# ww101board.net
KiCad netlist of a schematic drawn in EAGLE
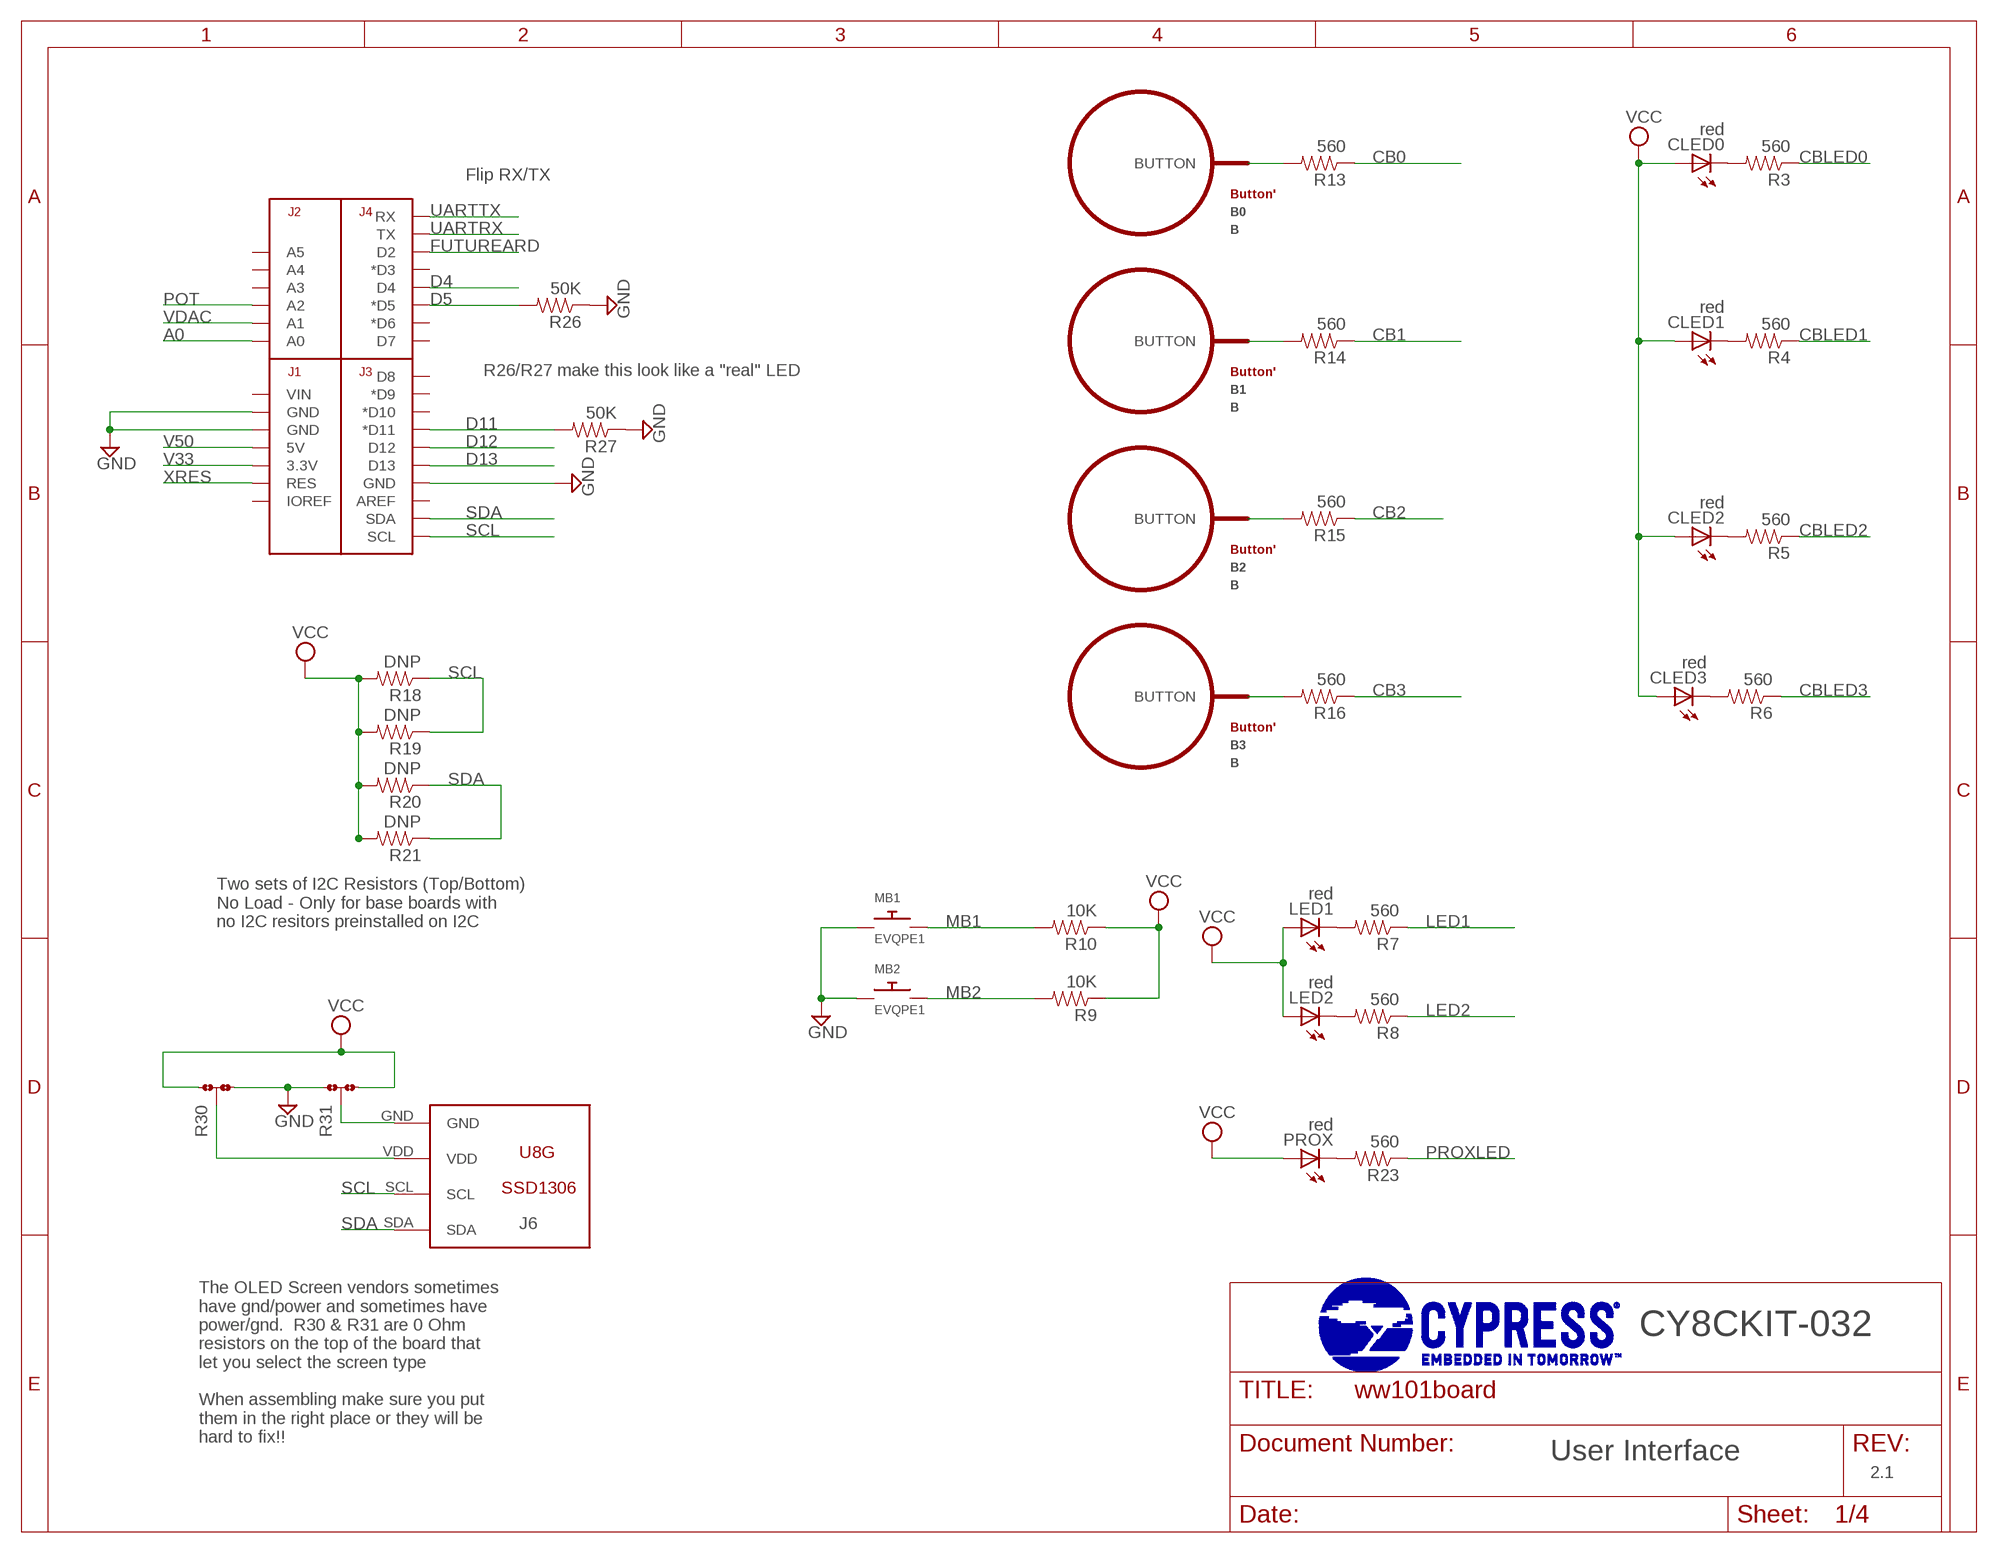
[diagram p0: schematic, sheet 1]
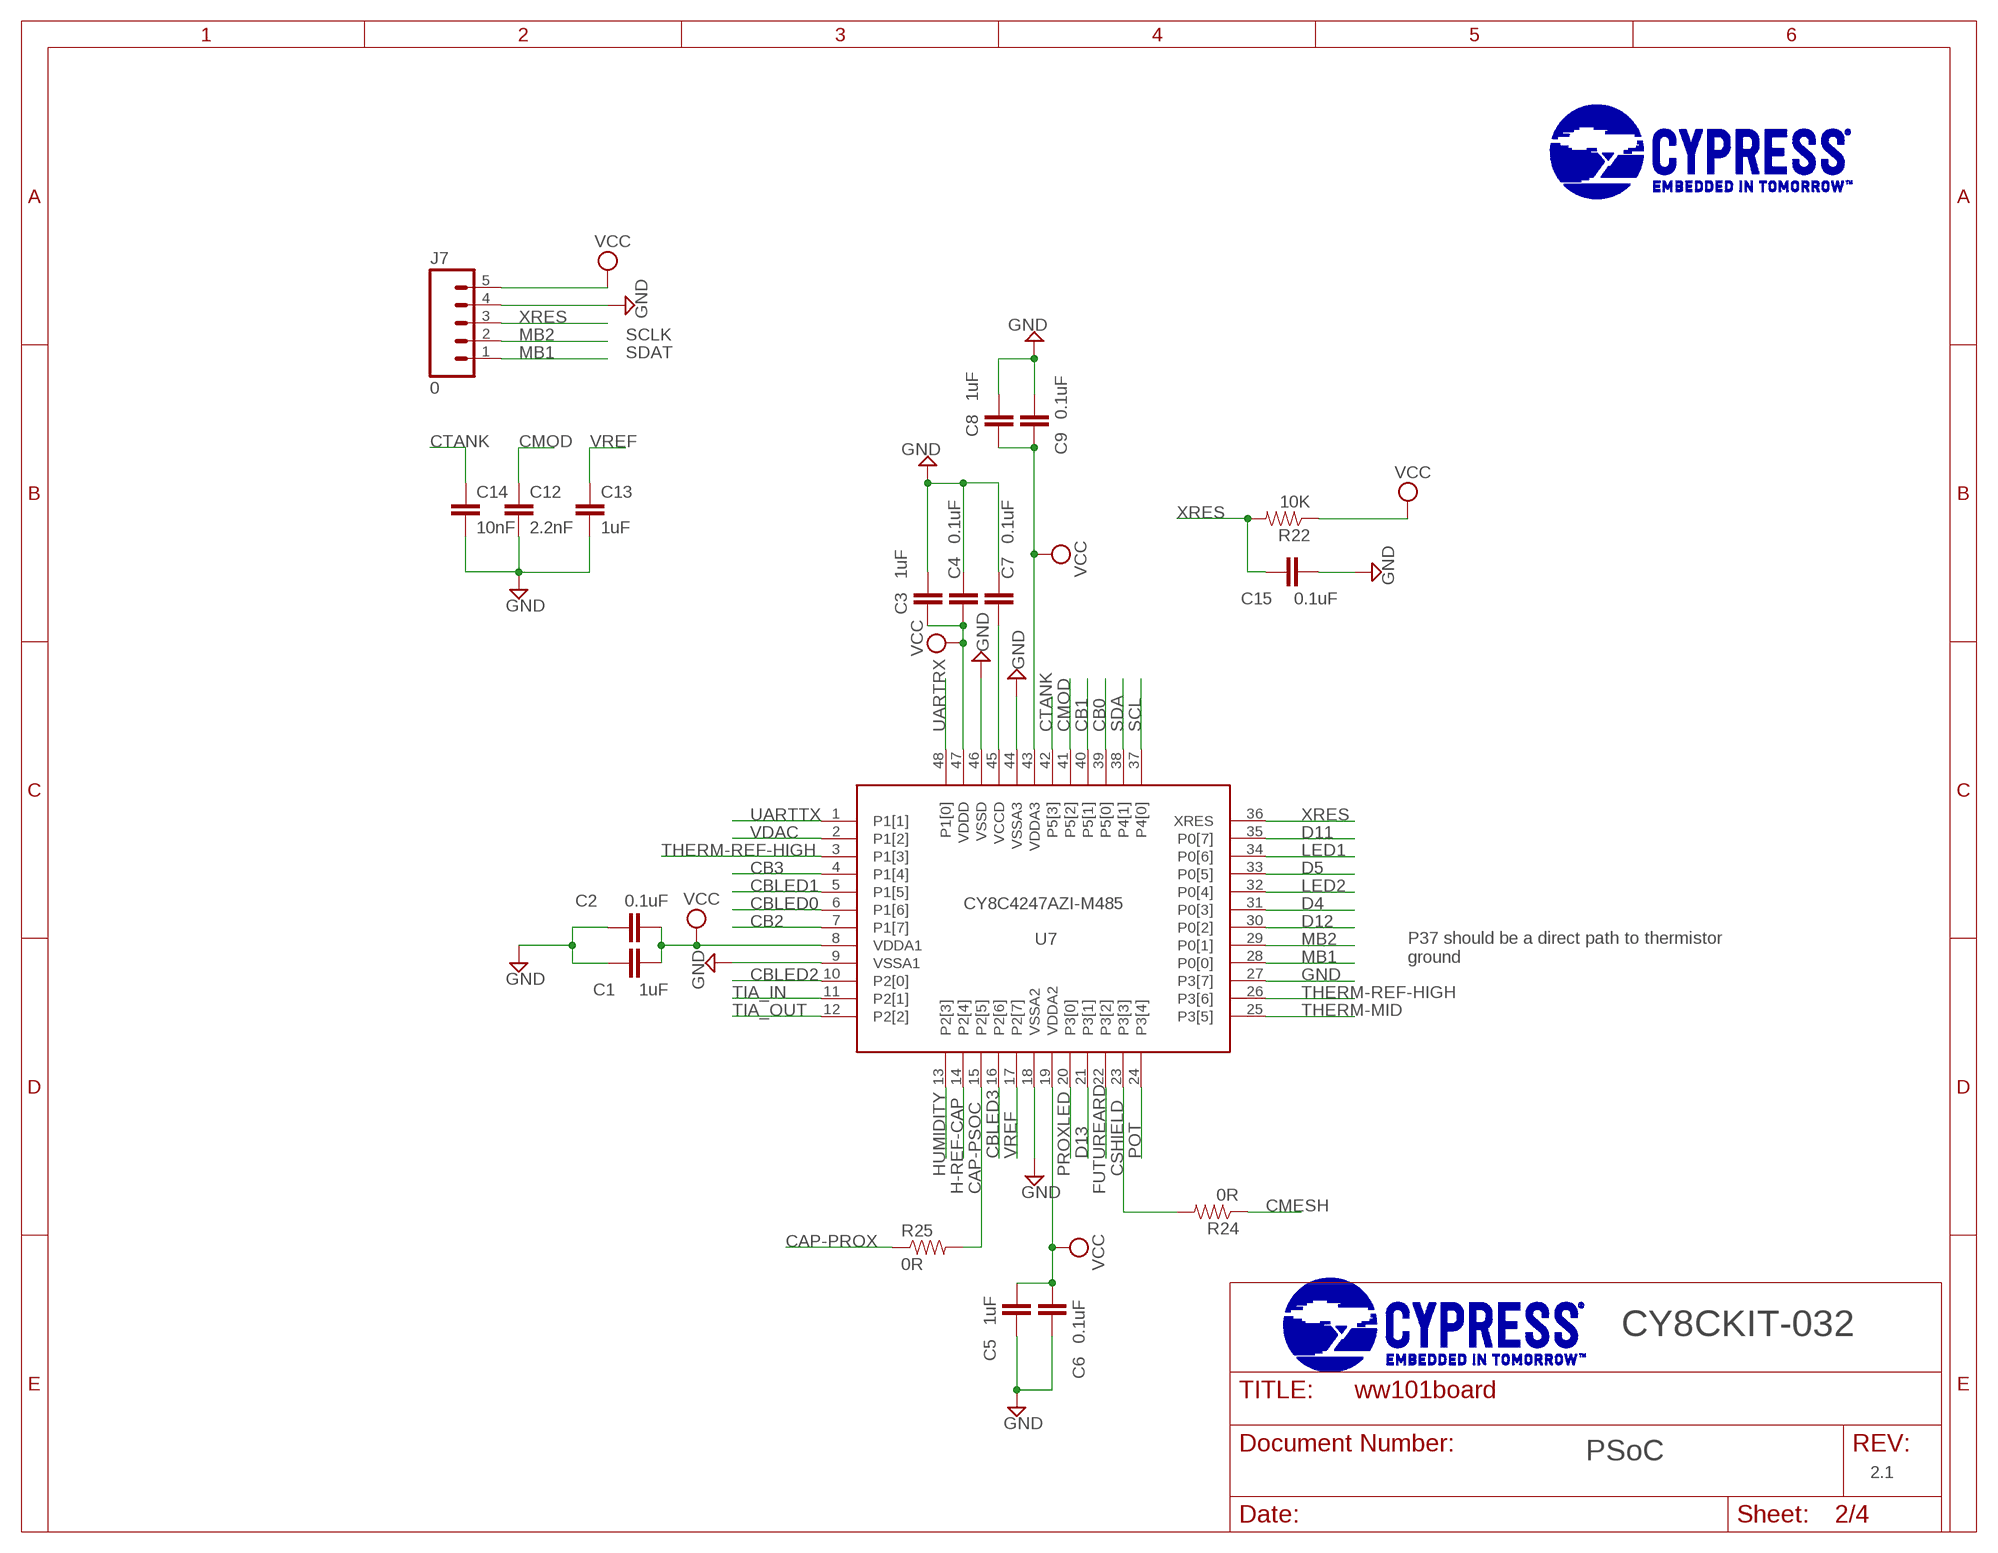
[diagram p1: schematic, sheet 2]
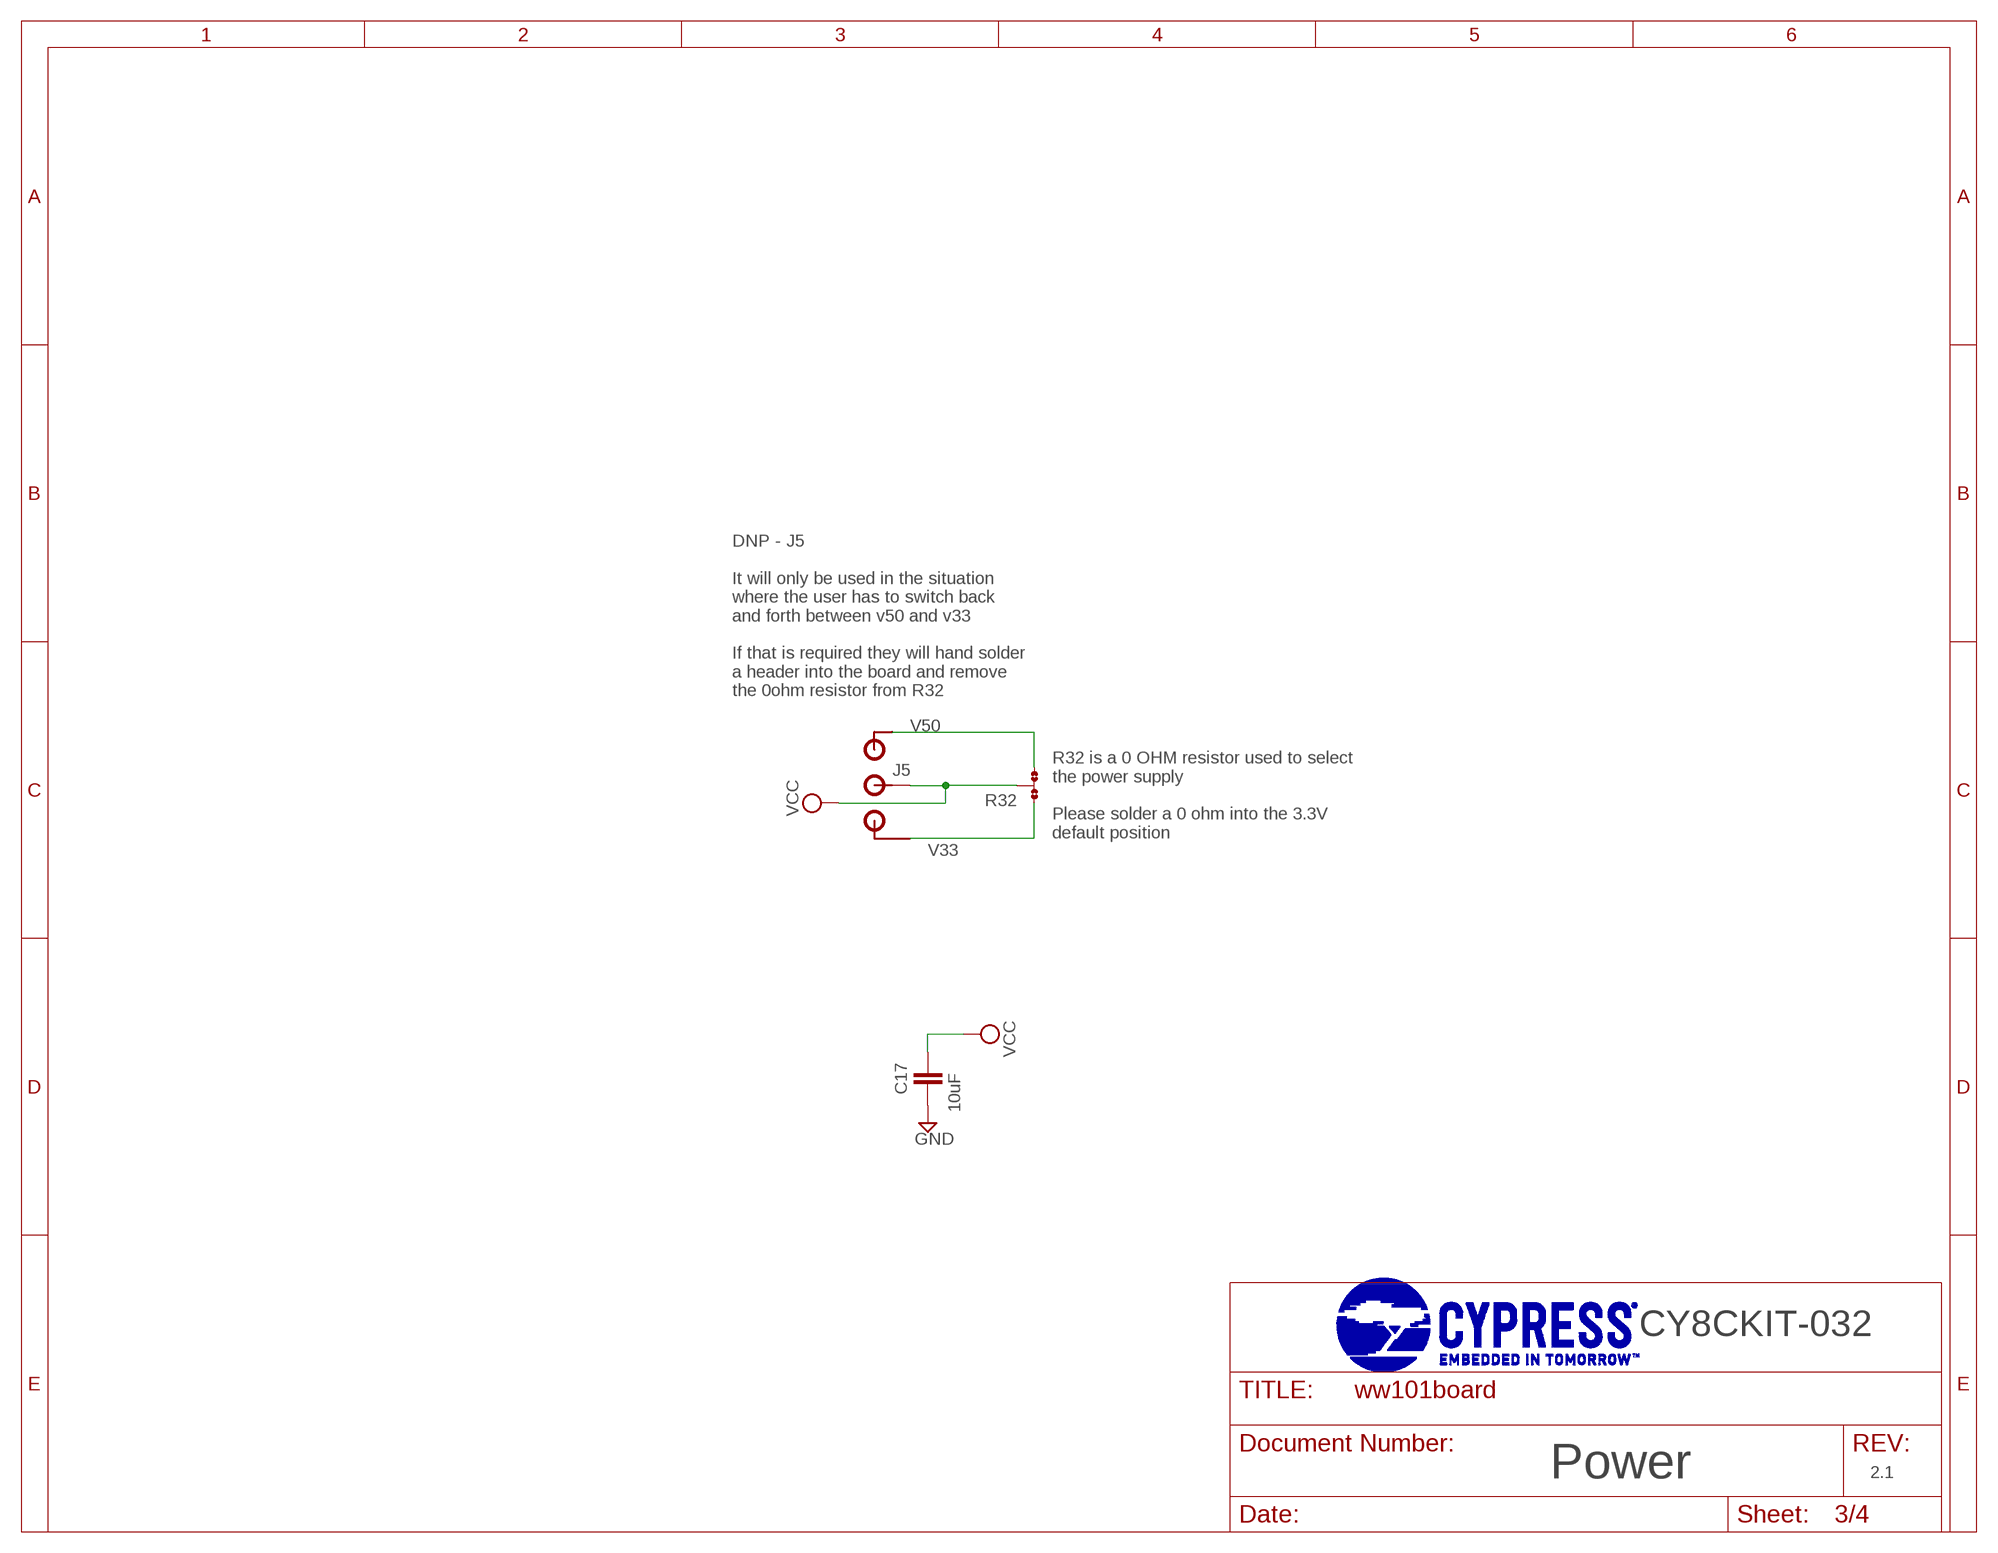
[diagram p2: schematic, sheet 3]
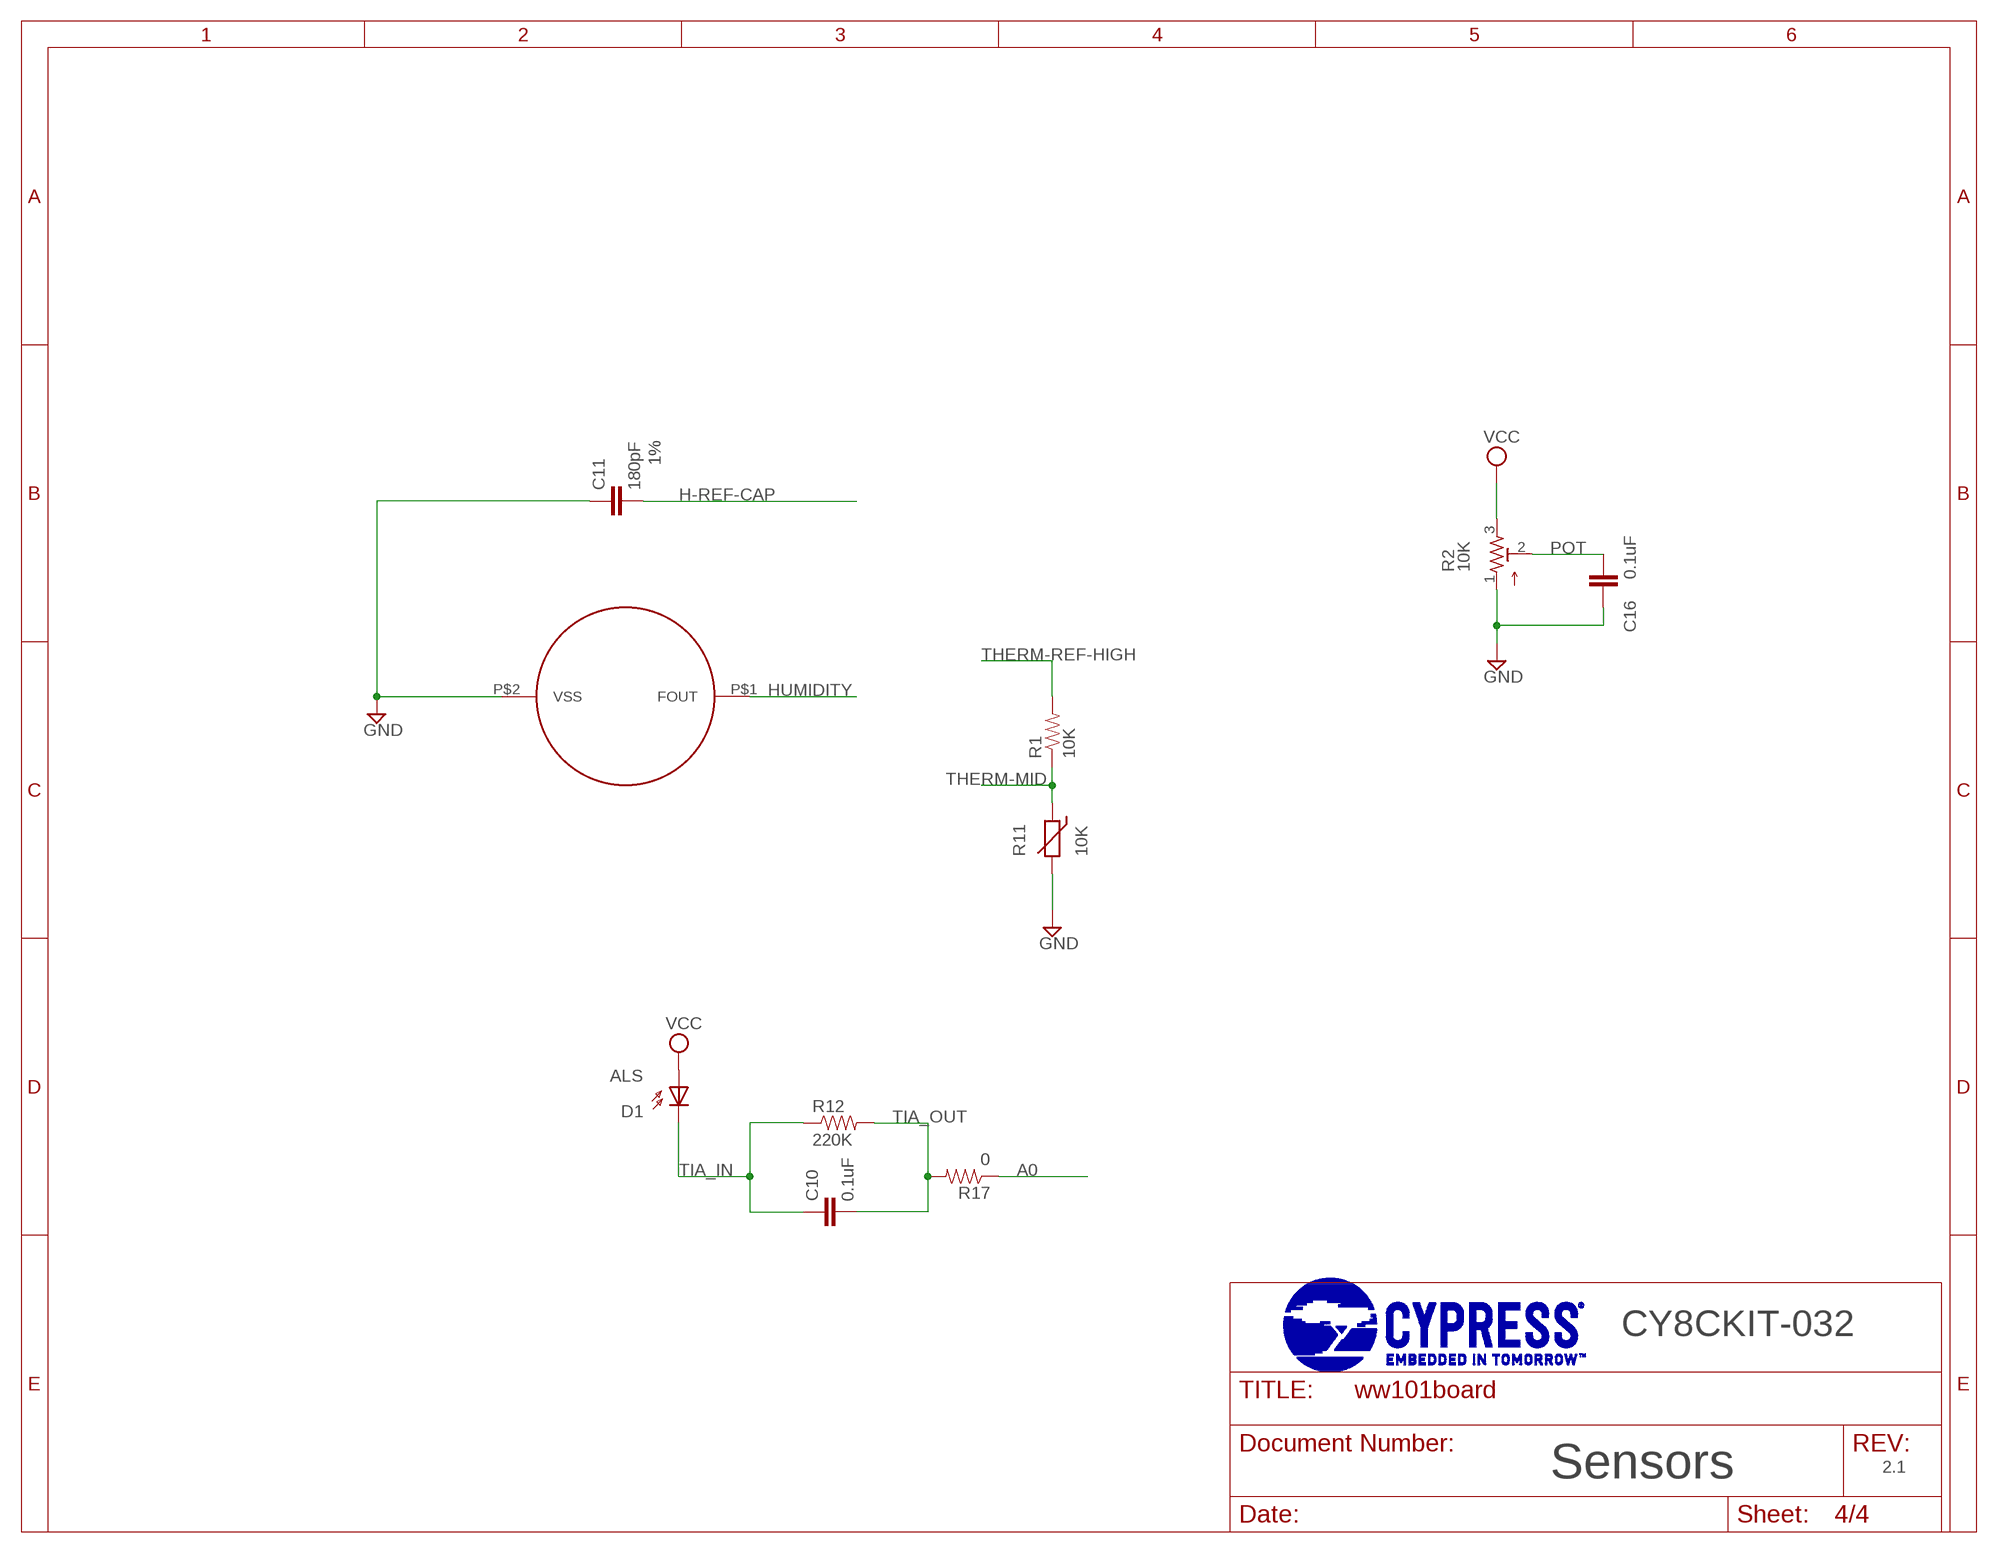
[diagram p3: schematic, sheet 4]

(export (version "E")
  (design (tool "Eeschema 10.0.6"))
  (components
    (comp (ref "C10")
      (value "0.1uF")
      (footprint "eagle-import:0603-CAP")
      (libsource (lib "eagle-import") (part "CAP0603-CAP"))
    )
    (comp (ref "C11")
      (value "180pF")
      (footprint "eagle-import:0603-CAP")
      (libsource (lib "eagle-import") (part "CAP0603-CAP"))
    )
    (comp (ref "C16")
      (value "0.1uF")
      (footprint "eagle-import:0603-CAP")
      (libsource (lib "eagle-import") (part "CAP0603-CAP"))
    )
    (comp (ref "D1")
      (value "ALS")
      (footprint "eagle-import:ALS")
      (libsource (lib "eagle-import") (part "ALS"))
    )
    (comp (ref "HUMIDITY")
      (value "HPP801A031")
      (footprint "eagle-import:HUMIDITY")
      (libsource (lib "eagle-import") (part "HPP801A031"))
    )
    (comp (ref "R1")
      (value "10K")
      (footprint "eagle-import:0603-RES")
      (libsource (lib "eagle-import") (part "RESISTOR0603"))
    )
    (comp (ref "R2")
      (value "10K")
      (footprint "eagle-import:3386P")
      (libsource (lib "eagle-import") (part "TRIM_US-3386P"))
    )
    (comp (ref "R11")
      (value "THERMISTOR-5")
      (footprint "eagle-import:R-5")
      (libsource (lib "eagle-import") (part "THERMISTOR-5"))
    )
    (comp (ref "R12")
      (value "220K")
      (footprint "eagle-import:0603-RES")
      (libsource (lib "eagle-import") (part "RESISTOR0603"))
    )
    (comp (ref "R17")
      (value "0")
      (footprint "eagle-import:0603-RES")
      (libsource (lib "eagle-import") (part "RESISTOR0603"))
    )
    (comp (ref "B0")
      (value "B")
      (footprint "eagle-import:BUTTON_PASSIVE_10MM")
      (libsource (lib "eagle-import") (part "BUTTON_PASSIVE10MM"))
    )
    (comp (ref "B1")
      (value "B")
      (footprint "eagle-import:BUTTON_PASSIVE_10MM")
      (libsource (lib "eagle-import") (part "BUTTON_PASSIVE10MM"))
    )
    (comp (ref "B2")
      (value "B")
      (footprint "eagle-import:BUTTON_PASSIVE_10MM")
      (libsource (lib "eagle-import") (part "BUTTON_PASSIVE10MM"))
    )
    (comp (ref "B3")
      (value "B")
      (footprint "eagle-import:BUTTON_PASSIVE_10MM")
      (libsource (lib "eagle-import") (part "BUTTON_PASSIVE10MM"))
    )
    (comp (ref "CLED0")
      (value "red")
      (footprint "eagle-import:CHIP-LED0603")
      (libsource (lib "eagle-import") (part "LEDCHIP-LED0603"))
    )
    (comp (ref "CLED1")
      (value "red")
      (footprint "eagle-import:CHIP-LED0603")
      (libsource (lib "eagle-import") (part "LEDCHIP-LED0603"))
    )
    (comp (ref "CLED2")
      (value "red")
      (footprint "eagle-import:CHIP-LED0603")
      (libsource (lib "eagle-import") (part "LEDCHIP-LED0603"))
    )
    (comp (ref "CLED3")
      (value "red")
      (footprint "eagle-import:CHIP-LED0603")
      (libsource (lib "eagle-import") (part "LEDCHIP-LED0603"))
    )
    (comp (ref "J6")
      (value "U8G-096-OLED")
      (footprint "eagle-import:096-SSD1306")
      (libsource (lib "eagle-import") (part "U8G-096-OLED"))
    )
    (comp (ref "LED1")
      (value "red")
      (footprint "eagle-import:CHIP-LED0603")
      (libsource (lib "eagle-import") (part "LEDCHIP-LED0603"))
    )
    (comp (ref "LED2")
      (value "red")
      (footprint "eagle-import:CHIP-LED0603")
      (libsource (lib "eagle-import") (part "LEDCHIP-LED0603"))
    )
    (comp (ref "MB1")
      (value "EVQPE1")
      (footprint "eagle-import:SWITCH")
      (libsource (lib "eagle-import") (part "EVQPE1"))
    )
    (comp (ref "MB2")
      (value "EVQPE1")
      (footprint "eagle-import:SWITCH")
      (libsource (lib "eagle-import") (part "EVQPE1"))
    )
    (comp (ref "PROX")
      (value "red")
      (footprint "eagle-import:CHIP-LED0603")
      (libsource (lib "eagle-import") (part "LEDCHIP-LED0603"))
    )
    (comp (ref "R3")
      (value "560")
      (footprint "eagle-import:0603-RES")
      (libsource (lib "eagle-import") (part "RESISTOR0603"))
    )
    (comp (ref "R4")
      (value "560")
      (footprint "eagle-import:0603-RES")
      (libsource (lib "eagle-import") (part "RESISTOR0603"))
    )
    (comp (ref "R5")
      (value "560")
      (footprint "eagle-import:0603-RES")
      (libsource (lib "eagle-import") (part "RESISTOR0603"))
    )
    (comp (ref "R6")
      (value "560")
      (footprint "eagle-import:0603-RES")
      (libsource (lib "eagle-import") (part "RESISTOR0603"))
    )
    (comp (ref "R7")
      (value "560")
      (footprint "eagle-import:0603-RES")
      (libsource (lib "eagle-import") (part "RESISTOR0603"))
    )
    (comp (ref "R8")
      (value "560")
      (footprint "eagle-import:0603-RES")
      (libsource (lib "eagle-import") (part "RESISTOR0603"))
    )
    (comp (ref "R9")
      (value "10K")
      (footprint "eagle-import:0603-RES")
      (libsource (lib "eagle-import") (part "RESISTOR0603"))
    )
    (comp (ref "R10")
      (value "10K")
      (footprint "eagle-import:0603-RES")
      (libsource (lib "eagle-import") (part "RESISTOR0603"))
    )
    (comp (ref "R13")
      (value "560")
      (footprint "eagle-import:0603-RES")
      (libsource (lib "eagle-import") (part "RESISTOR0603"))
    )
    (comp (ref "R14")
      (value "560")
      (footprint "eagle-import:0603-RES")
      (libsource (lib "eagle-import") (part "RESISTOR0603"))
    )
    (comp (ref "R15")
      (value "560")
      (footprint "eagle-import:0603-RES")
      (libsource (lib "eagle-import") (part "RESISTOR0603"))
    )
    (comp (ref "R16")
      (value "560")
      (footprint "eagle-import:0603-RES")
      (libsource (lib "eagle-import") (part "RESISTOR0603"))
    )
    (comp (ref "R18")
      (value "DNP")
      (footprint "eagle-import:0603-RES")
      (libsource (lib "eagle-import") (part "RESISTOR0603"))
    )
    (comp (ref "R19")
      (value "DNP")
      (footprint "eagle-import:0603-RES")
      (libsource (lib "eagle-import") (part "RESISTOR0603"))
    )
    (comp (ref "R20")
      (value "DNP")
      (footprint "eagle-import:0603-RES")
      (libsource (lib "eagle-import") (part "RESISTOR0603"))
    )
    (comp (ref "R21")
      (value "DNP")
      (footprint "eagle-import:0603-RES")
      (libsource (lib "eagle-import") (part "RESISTOR0603"))
    )
    (comp (ref "R23")
      (value "560")
      (footprint "eagle-import:0603-RES")
      (libsource (lib "eagle-import") (part "RESISTOR0603"))
    )
    (comp (ref "R26")
      (value "50K")
      (footprint "eagle-import:0603-RES")
      (libsource (lib "eagle-import") (part "RESISTOR0603"))
    )
    (comp (ref "R27")
      (value "50K")
      (footprint "eagle-import:0603-RES")
      (libsource (lib "eagle-import") (part "RESISTOR0603"))
    )
    (comp (ref "R30")
      (value "JMP-3-1_2")
      (footprint "eagle-import:JMP-3-1_2")
      (libsource (lib "eagle-import") (part "JMP-3-1_2"))
    )
    (comp (ref "R31")
      (value "JMP-3-2_3")
      (footprint "eagle-import:JMP-3-2_3")
      (libsource (lib "eagle-import") (part "JMP-3-2_3"))
    )
    (comp (ref "U$1")
      (value "ARDUINO_R3_SHIELDNOLABELS")
      (footprint "eagle-import:UNO_R3_SHIELD_NOLABELS")
      (libsource (lib "eagle-import") (part "ARDUINO_R3_SHIELDNOLABELS"))
    )
    (comp (ref "C1")
      (value "1uF")
      (footprint "eagle-import:0603-CAP")
      (libsource (lib "eagle-import") (part "CAP0603-CAP"))
    )
    (comp (ref "C2")
      (value "0.1uF")
      (footprint "eagle-import:0603-CAP")
      (libsource (lib "eagle-import") (part "CAP0603-CAP"))
    )
    (comp (ref "C3")
      (value "1uF")
      (footprint "eagle-import:0603-CAP")
      (libsource (lib "eagle-import") (part "CAP0603-CAP"))
    )
    (comp (ref "C4")
      (value "0.1uF")
      (footprint "eagle-import:0603-CAP")
      (libsource (lib "eagle-import") (part "CAP0603-CAP"))
    )
    (comp (ref "C5")
      (value "1uF")
      (footprint "eagle-import:0603-CAP")
      (libsource (lib "eagle-import") (part "CAP0603-CAP"))
    )
    (comp (ref "C6")
      (value "0.1uF")
      (footprint "eagle-import:0603-CAP")
      (libsource (lib "eagle-import") (part "CAP0603-CAP"))
    )
    (comp (ref "C7")
      (value "0.1uF")
      (footprint "eagle-import:0603-CAP")
      (libsource (lib "eagle-import") (part "CAP0603-CAP"))
    )
    (comp (ref "C8")
      (value "1uF")
      (footprint "eagle-import:0603-CAP")
      (libsource (lib "eagle-import") (part "CAP0603-CAP"))
    )
    (comp (ref "C9")
      (value "0.1uF")
      (footprint "eagle-import:0603-CAP")
      (libsource (lib "eagle-import") (part "CAP0603-CAP"))
    )
    (comp (ref "C12")
      (value "2.2nF")
      (footprint "eagle-import:0603-CAP")
      (libsource (lib "eagle-import") (part "CAP0603-CAP"))
    )
    (comp (ref "C13")
      (value "1uF")
      (footprint "eagle-import:0603-CAP")
      (libsource (lib "eagle-import") (part "CAP0603-CAP"))
    )
    (comp (ref "C14")
      (value "10nF")
      (footprint "eagle-import:0603-CAP")
      (libsource (lib "eagle-import") (part "CAP0603-CAP"))
    )
    (comp (ref "C15")
      (value "0.1uF")
      (footprint "eagle-import:0603-CAP")
      (libsource (lib "eagle-import") (part "CAP0603-CAP"))
    )
    (comp (ref "J7")
      (value "0")
      (footprint "eagle-import:1X05_LOCK")
      (libsource (lib "eagle-import") (part "M05LOCK"))
    )
    (comp (ref "R22")
      (value "10K")
      (footprint "eagle-import:0603-RES")
      (libsource (lib "eagle-import") (part "RESISTOR0603"))
    )
    (comp (ref "R24")
      (value "0R")
      (footprint "eagle-import:0603-RES")
      (libsource (lib "eagle-import") (part "RESISTOR0603"))
    )
    (comp (ref "R25")
      (value "0R")
      (footprint "eagle-import:0603-RES")
      (libsource (lib "eagle-import") (part "RESISTOR0603"))
    )
    (comp (ref "U$7")
      (value "CYLOGO-SILK")
      (footprint "eagle-import:CYLOGO-SILK")
      (libsource (lib "eagle-import") (part "CYLOGO-SILK"))
    )
    (comp (ref "U7")
      (value "CY8C4A45-48")
      (footprint "eagle-import:TQFP-7X7-48")
      (libsource (lib "eagle-import") (part "CY8C4A45-48"))
    )
    (comp (ref "C17")
      (value "10uF")
      (footprint "eagle-import:0603-CAP")
      (libsource (lib "eagle-import") (part "CAP0603-CAP"))
    )
    (comp (ref "J5")
      (value "JMP-3-PTH-PTH")
      (footprint "eagle-import:JMP-3-NO-PTH-2.54")
      (libsource (lib "eagle-import") (part "JMP-3-PTH-PTH"))
    )
    (comp (ref "R32")
      (value "JMP-3-NO")
      (footprint "eagle-import:JMP-3-NO")
      (libsource (lib "eagle-import") (part "JMP-3-NO"))
    )
  )
  (nets
    (net (code "1") (name "A0") (class "Default")
      (node (ref "R17") (pin "1") (pinfunction "1_1") (pintype "passive"))
      (node (ref "U$1") (pin "A0") (pinfunction "A0_A0") (pintype "bidirectional"))
    )
    (net (code "2") (name "CAP-PROX") (class "Default")
      (node (ref "R25") (pin "1") (pinfunction "1_1") (pintype "passive"))
    )
    (net (code "3") (name "CAP-PSOC") (class "Default")
      (node (ref "R25") (pin "2") (pinfunction "2_2") (pintype "passive"))
      (node (ref "U7") (pin "15") (pinfunction "P2[5]_15") (pintype "bidirectional"))
    )
    (net (code "4") (name "CB0") (class "Default")
      (node (ref "R13") (pin "1") (pinfunction "1_1") (pintype "passive"))
      (node (ref "U7") (pin "39") (pinfunction "P5[0]_39") (pintype "bidirectional"))
    )
    (net (code "5") (name "CB1") (class "Default")
      (node (ref "R14") (pin "1") (pinfunction "1_1") (pintype "passive"))
      (node (ref "U7") (pin "40") (pinfunction "P5[1]_40") (pintype "bidirectional"))
    )
    (net (code "6") (name "CB2") (class "Default")
      (node (ref "R15") (pin "1") (pinfunction "1_1") (pintype "passive"))
      (node (ref "U7") (pin "7") (pinfunction "P1[7]_7") (pintype "bidirectional"))
    )
    (net (code "7") (name "CB3") (class "Default")
      (node (ref "R16") (pin "1") (pinfunction "1_1") (pintype "passive"))
      (node (ref "U7") (pin "4") (pinfunction "P1[4]_4") (pintype "bidirectional"))
    )
    (net (code "8") (name "CBLED0") (class "Default")
      (node (ref "R3") (pin "1") (pinfunction "1_1") (pintype "passive"))
      (node (ref "U7") (pin "6") (pinfunction "P1[6]_6") (pintype "bidirectional"))
    )
    (net (code "9") (name "CBLED1") (class "Default")
      (node (ref "R4") (pin "1") (pinfunction "1_1") (pintype "passive"))
      (node (ref "U7") (pin "5") (pinfunction "P1[5]_5") (pintype "bidirectional"))
    )
    (net (code "10") (name "CBLED2") (class "Default")
      (node (ref "R5") (pin "1") (pinfunction "1_1") (pintype "passive"))
      (node (ref "U7") (pin "10") (pinfunction "P2[0]_10") (pintype "bidirectional"))
    )
    (net (code "11") (name "CBLED3") (class "Default")
      (node (ref "R6") (pin "1") (pinfunction "1_1") (pintype "passive"))
      (node (ref "U7") (pin "16") (pinfunction "P2[6]_16") (pintype "bidirectional"))
    )
    (net (code "12") (name "CMESH") (class "Default")
      (node (ref "R24") (pin "1") (pinfunction "1_1") (pintype "passive"))
    )
    (net (code "13") (name "CMOD") (class "Default")
      (node (ref "C12") (pin "1") (pinfunction "1_1") (pintype "passive"))
      (node (ref "U7") (pin "41") (pinfunction "P5[2]_41") (pintype "bidirectional"))
    )
    (net (code "14") (name "CSHIELD") (class "Default")
      (node (ref "R24") (pin "2") (pinfunction "2_2") (pintype "passive"))
      (node (ref "U7") (pin "23") (pinfunction "P3[3]_23") (pintype "bidirectional"))
    )
    (net (code "15") (name "CTANK") (class "Default")
      (node (ref "C14") (pin "1") (pinfunction "1_1") (pintype "passive"))
      (node (ref "U7") (pin "42") (pinfunction "P5[3]_42") (pintype "bidirectional"))
    )
    (net (code "16") (name "D4") (class "Default")
      (node (ref "U$1") (pin "D4") (pinfunction "D4_D4") (pintype "bidirectional"))
      (node (ref "U7") (pin "31") (pinfunction "P0[3]_31") (pintype "bidirectional"))
    )
    (net (code "17") (name "D5") (class "Default")
      (node (ref "R26") (pin "2") (pinfunction "2_2") (pintype "passive"))
      (node (ref "U$1") (pin "D5") (pinfunction "*D5_D5") (pintype "bidirectional"))
      (node (ref "U7") (pin "33") (pinfunction "P0[5]_33") (pintype "bidirectional"))
    )
    (net (code "18") (name "D11") (class "Default")
      (node (ref "R27") (pin "2") (pinfunction "2_2") (pintype "passive"))
      (node (ref "U$1") (pin "D11") (pinfunction "*D11_D11") (pintype "bidirectional"))
      (node (ref "U7") (pin "35") (pinfunction "P0[7]_35") (pintype "bidirectional"))
    )
    (net (code "19") (name "D12") (class "Default")
      (node (ref "U$1") (pin "D12") (pinfunction "D12_D12") (pintype "bidirectional"))
      (node (ref "U7") (pin "30") (pinfunction "P0[2]_30") (pintype "bidirectional"))
    )
    (net (code "20") (name "D13") (class "Default")
      (node (ref "U$1") (pin "D13") (pinfunction "D13_D13") (pintype "bidirectional"))
      (node (ref "U7") (pin "21") (pinfunction "P3[1]_21") (pintype "bidirectional"))
    )
    (net (code "21") (name "FUTUREARD") (class "Default")
      (node (ref "U$1") (pin "D2") (pinfunction "D2_D2") (pintype "bidirectional"))
      (node (ref "U7") (pin "22") (pinfunction "P3[2]_22") (pintype "bidirectional"))
    )
    (net (code "22") (name "GND") (class "Default")
      (node (ref "C1") (pin "1") (pinfunction "1_1") (pintype "passive"))
      (node (ref "C11") (pin "1") (pinfunction "1_1") (pintype "passive"))
      (node (ref "C12") (pin "2") (pinfunction "2_2") (pintype "passive"))
      (node (ref "C13") (pin "2") (pinfunction "2_2") (pintype "passive"))
      (node (ref "C14") (pin "2") (pinfunction "2_2") (pintype "passive"))
      (node (ref "C15") (pin "1") (pinfunction "1_1") (pintype "passive"))
      (node (ref "C16") (pin "2") (pinfunction "2_2") (pintype "passive"))
      (node (ref "C17") (pin "2") (pinfunction "2_2") (pintype "passive"))
      (node (ref "C2") (pin "1") (pinfunction "1_1") (pintype "passive"))
      (node (ref "C3") (pin "1") (pinfunction "1_1") (pintype "passive"))
      (node (ref "C4") (pin "1") (pinfunction "1_1") (pintype "passive"))
      (node (ref "C5") (pin "2") (pinfunction "2_2") (pintype "passive"))
      (node (ref "C6") (pin "2") (pinfunction "2_2") (pintype "passive"))
      (node (ref "C7") (pin "1") (pinfunction "1_1") (pintype "passive"))
      (node (ref "C8") (pin "1") (pinfunction "1_1") (pintype "passive"))
      (node (ref "C9") (pin "1") (pinfunction "1_1") (pintype "passive"))
      (node (ref "HUMIDITY") (pin "P$2") (pinfunction "VSS_P$2") (pintype "bidirectional"))
      (node (ref "J7") (pin "4") (pinfunction "4_4") (pintype "passive"))
      (node (ref "MB1") (pin "P$1") (pinfunction "P$1_P$1") (pintype "passive"))
      (node (ref "MB2") (pin "P$1") (pinfunction "P$1_P$1") (pintype "passive"))
      (node (ref "R11") (pin "2") (pinfunction "2_2") (pintype "passive"))
      (node (ref "R2") (pin "1") (pinfunction "1_1") (pintype "passive"))
      (node (ref "R26") (pin "1") (pinfunction "1_1") (pintype "passive"))
      (node (ref "R27") (pin "1") (pinfunction "1_1") (pintype "passive"))
      (node (ref "R30") (pin "3") (pinfunction "3_3") (pintype "passive"))
      (node (ref "R31") (pin "1") (pinfunction "1_1") (pintype "passive"))
      (node (ref "U$1") (pin "GND@0") (pinfunction "GND_GND@0") (pintype "bidirectional"))
      (node (ref "U$1") (pin "GND@1") (pinfunction "GND_GND@1") (pintype "bidirectional"))
      (node (ref "U$1") (pin "GND@2") (pinfunction "GND_GND@2") (pintype "bidirectional"))
      (node (ref "U7") (pin "18") (pinfunction "VSSA2_18") (pintype "bidirectional"))
      (node (ref "U7") (pin "27") (pinfunction "P3[7]_27") (pintype "bidirectional"))
      (node (ref "U7") (pin "44") (pinfunction "VSSA3_44") (pintype "bidirectional"))
      (node (ref "U7") (pin "46") (pinfunction "VSSD_46") (pintype "bidirectional"))
      (node (ref "U7") (pin "9") (pinfunction "VSSA1_9") (pintype "bidirectional"))
    )
    (net (code "23") (name "H-REF-CAP") (class "Default")
      (node (ref "C11") (pin "2") (pinfunction "2_2") (pintype "passive"))
      (node (ref "U7") (pin "14") (pinfunction "P2[4]_14") (pintype "bidirectional"))
    )
    (net (code "24") (name "HUMIDITY") (class "Default")
      (node (ref "HUMIDITY") (pin "P$1") (pinfunction "FOUT_P$1") (pintype "bidirectional"))
      (node (ref "U7") (pin "13") (pinfunction "P2[3]_13") (pintype "bidirectional"))
    )
    (net (code "25") (name "LED1") (class "Default")
      (node (ref "R7") (pin "1") (pinfunction "1_1") (pintype "passive"))
      (node (ref "U7") (pin "34") (pinfunction "P0[6]_34") (pintype "bidirectional"))
    )
    (net (code "26") (name "LED2") (class "Default")
      (node (ref "R8") (pin "1") (pinfunction "1_1") (pintype "passive"))
      (node (ref "U7") (pin "32") (pinfunction "P0[4]_32") (pintype "bidirectional"))
    )
    (net (code "27") (name "MB1") (class "Default")
      (node (ref "J7") (pin "1") (pinfunction "1_1") (pintype "passive"))
      (node (ref "MB1") (pin "P$2") (pinfunction "P$2_P$2") (pintype "passive"))
      (node (ref "R10") (pin "2") (pinfunction "2_2") (pintype "passive"))
      (node (ref "U7") (pin "28") (pinfunction "P0[0]_28") (pintype "bidirectional"))
    )
    (net (code "28") (name "MB2") (class "Default")
      (node (ref "J7") (pin "2") (pinfunction "2_2") (pintype "passive"))
      (node (ref "MB2") (pin "P$2") (pinfunction "P$2_P$2") (pintype "passive"))
      (node (ref "R9") (pin "2") (pinfunction "2_2") (pintype "passive"))
      (node (ref "U7") (pin "29") (pinfunction "P0[1]_29") (pintype "bidirectional"))
    )
    (net (code "29") (name "Net-(B0-PadBUTTON)") (class "Default")
      (node (ref "B0") (pin "BUTTON") (pinfunction "BUTTON_BUTTON") (pintype "passive"))
      (node (ref "R13") (pin "2") (pinfunction "2_2") (pintype "passive"))
    )
    (net (code "30") (name "Net-(B1-PadBUTTON)") (class "Default")
      (node (ref "B1") (pin "BUTTON") (pinfunction "BUTTON_BUTTON") (pintype "passive"))
      (node (ref "R14") (pin "2") (pinfunction "2_2") (pintype "passive"))
    )
    (net (code "31") (name "Net-(B2-PadBUTTON)") (class "Default")
      (node (ref "B2") (pin "BUTTON") (pinfunction "BUTTON_BUTTON") (pintype "passive"))
      (node (ref "R15") (pin "2") (pinfunction "2_2") (pintype "passive"))
    )
    (net (code "32") (name "Net-(B3-PadBUTTON)") (class "Default")
      (node (ref "B3") (pin "BUTTON") (pinfunction "BUTTON_BUTTON") (pintype "passive"))
      (node (ref "R16") (pin "2") (pinfunction "2_2") (pintype "passive"))
    )
    (net (code "33") (name "Net-(CLED0-PadC)") (class "Default")
      (node (ref "CLED0") (pin "C") (pinfunction "C_C") (pintype "passive"))
      (node (ref "R3") (pin "2") (pinfunction "2_2") (pintype "passive"))
    )
    (net (code "34") (name "Net-(CLED1-PadC)") (class "Default")
      (node (ref "CLED1") (pin "C") (pinfunction "C_C") (pintype "passive"))
      (node (ref "R4") (pin "2") (pinfunction "2_2") (pintype "passive"))
    )
    (net (code "35") (name "Net-(CLED2-PadC)") (class "Default")
      (node (ref "CLED2") (pin "C") (pinfunction "C_C") (pintype "passive"))
      (node (ref "R5") (pin "2") (pinfunction "2_2") (pintype "passive"))
    )
    (net (code "36") (name "Net-(CLED3-PadC)") (class "Default")
      (node (ref "CLED3") (pin "C") (pinfunction "C_C") (pintype "passive"))
      (node (ref "R6") (pin "2") (pinfunction "2_2") (pintype "passive"))
    )
    (net (code "37") (name "Net-(J6-PadGND)") (class "Default")
      (node (ref "J6") (pin "GND") (pinfunction "GND_GND") (pintype "power_in"))
      (node (ref "R31") (pin "2") (pinfunction "2_2") (pintype "passive"))
    )
    (net (code "38") (name "Net-(J6-PadVDD)") (class "Default")
      (node (ref "J6") (pin "VDD") (pinfunction "VDD_VDD") (pintype "power_in"))
      (node (ref "R30") (pin "2") (pinfunction "2_2") (pintype "passive"))
    )
    (net (code "39") (name "Net-(LED1-PadC)") (class "Default")
      (node (ref "LED1") (pin "C") (pinfunction "C_C") (pintype "passive"))
      (node (ref "R7") (pin "2") (pinfunction "2_2") (pintype "passive"))
    )
    (net (code "40") (name "Net-(LED2-PadC)") (class "Default")
      (node (ref "LED2") (pin "C") (pinfunction "C_C") (pintype "passive"))
      (node (ref "R8") (pin "2") (pinfunction "2_2") (pintype "passive"))
    )
    (net (code "41") (name "Net-(PROX-PadC)") (class "Default")
      (node (ref "PROX") (pin "C") (pinfunction "C_C") (pintype "passive"))
      (node (ref "R23") (pin "2") (pinfunction "2_2") (pintype "passive"))
    )
    (net (code "42") (name "Net-(U7-VCCD)") (class "Default")
      (node (ref "C7") (pin "2") (pinfunction "2_2") (pintype "passive"))
      (node (ref "U7") (pin "45") (pinfunction "VCCD_45") (pintype "bidirectional"))
    )
    (net (code "43") (name "POT") (class "Default")
      (node (ref "C16") (pin "1") (pinfunction "1_1") (pintype "passive"))
      (node (ref "R2") (pin "2") (pinfunction "2_2") (pintype "passive"))
      (node (ref "U$1") (pin "A2") (pinfunction "A2_A2") (pintype "bidirectional"))
      (node (ref "U7") (pin "24") (pinfunction "P3[4]_24") (pintype "bidirectional"))
    )
    (net (code "44") (name "PROXLED") (class "Default")
      (node (ref "R23") (pin "1") (pinfunction "1_1") (pintype "passive"))
      (node (ref "U7") (pin "20") (pinfunction "P3[0]_20") (pintype "bidirectional"))
    )
    (net (code "45") (name "SCL") (class "Default")
      (node (ref "J6") (pin "SCL") (pinfunction "SCL_SCL") (pintype "bidirectional"))
      (node (ref "R18") (pin "1") (pinfunction "1_1") (pintype "passive"))
      (node (ref "R19") (pin "1") (pinfunction "1_1") (pintype "passive"))
      (node (ref "U$1") (pin "SCL") (pinfunction "SCL_SCL") (pintype "bidirectional"))
      (node (ref "U7") (pin "37") (pinfunction "P4[0]_37") (pintype "bidirectional"))
    )
    (net (code "46") (name "SDA") (class "Default")
      (node (ref "J6") (pin "SDA") (pinfunction "SDA_SDA") (pintype "bidirectional"))
      (node (ref "R20") (pin "1") (pinfunction "1_1") (pintype "passive"))
      (node (ref "R21") (pin "1") (pinfunction "1_1") (pintype "passive"))
      (node (ref "U$1") (pin "SDA") (pinfunction "SDA_SDA") (pintype "bidirectional"))
      (node (ref "U7") (pin "38") (pinfunction "P4[1]_38") (pintype "bidirectional"))
    )
    (net (code "47") (name "THERM-MID") (class "Default")
      (node (ref "R1") (pin "1") (pinfunction "1_1") (pintype "passive"))
      (node (ref "R11") (pin "1") (pinfunction "1_1") (pintype "passive"))
      (node (ref "U7") (pin "25") (pinfunction "P3[5]_25") (pintype "bidirectional"))
    )
    (net (code "48") (name "THERM-REF-HIGH") (class "Default")
      (node (ref "R1") (pin "2") (pinfunction "2_2") (pintype "passive"))
      (node (ref "U7") (pin "26") (pinfunction "P3[6]_26") (pintype "bidirectional"))
      (node (ref "U7") (pin "3") (pinfunction "P1[3]_3") (pintype "bidirectional"))
    )
    (net (code "49") (name "TIA_IN") (class "Default")
      (node (ref "C10") (pin "1") (pinfunction "1_1") (pintype "passive"))
      (node (ref "D1") (pin "CATHODE") (pinfunction "C1_CATHODE") (pintype "passive"))
      (node (ref "R12") (pin "1") (pinfunction "1_1") (pintype "passive"))
      (node (ref "U7") (pin "11") (pinfunction "P2[1]_11") (pintype "bidirectional"))
    )
    (net (code "50") (name "TIA_OUT") (class "Default")
      (node (ref "C10") (pin "2") (pinfunction "2_2") (pintype "passive"))
      (node (ref "R12") (pin "2") (pinfunction "2_2") (pintype "passive"))
      (node (ref "R17") (pin "2") (pinfunction "2_2") (pintype "passive"))
      (node (ref "U7") (pin "12") (pinfunction "P2[2]_12") (pintype "bidirectional"))
    )
    (net (code "51") (name "UARTRX") (class "Default")
      (node (ref "U$1") (pin "TX") (pinfunction "TX_TX") (pintype "bidirectional"))
      (node (ref "U7") (pin "48") (pinfunction "P1[0]_48") (pintype "bidirectional"))
    )
    (net (code "52") (name "UARTTX") (class "Default")
      (node (ref "U$1") (pin "RX") (pinfunction "RX_RX") (pintype "bidirectional"))
      (node (ref "U7") (pin "1") (pinfunction "P1[1]_1") (pintype "bidirectional"))
    )
    (net (code "53") (name "V33") (class "Default")
      (node (ref "J5") (pin "3") (pinfunction "3_3") (pintype "passive"))
      (node (ref "R32") (pin "1") (pinfunction "1_1") (pintype "passive"))
      (node (ref "U$1") (pin "3.3V") (pinfunction "3.3V_3.3V") (pintype "bidirectional"))
    )
    (net (code "54") (name "V50") (class "Default")
      (node (ref "J5") (pin "1") (pinfunction "1_1") (pintype "passive"))
      (node (ref "R32") (pin "3") (pinfunction "3_3") (pintype "passive"))
      (node (ref "U$1") (pin "5V") (pinfunction "5V_5V") (pintype "bidirectional"))
    )
    (net (code "55") (name "VCC") (class "Default")
      (node (ref "C1") (pin "2") (pinfunction "2_2") (pintype "passive"))
      (node (ref "C17") (pin "1") (pinfunction "1_1") (pintype "passive"))
      (node (ref "C2") (pin "2") (pinfunction "2_2") (pintype "passive"))
      (node (ref "C3") (pin "2") (pinfunction "2_2") (pintype "passive"))
      (node (ref "C4") (pin "2") (pinfunction "2_2") (pintype "passive"))
      (node (ref "C5") (pin "1") (pinfunction "1_1") (pintype "passive"))
      (node (ref "C6") (pin "1") (pinfunction "1_1") (pintype "passive"))
      (node (ref "C8") (pin "2") (pinfunction "2_2") (pintype "passive"))
      (node (ref "C9") (pin "2") (pinfunction "2_2") (pintype "passive"))
      (node (ref "CLED0") (pin "A") (pinfunction "A_A") (pintype "passive"))
      (node (ref "CLED1") (pin "A") (pinfunction "A_A") (pintype "passive"))
      (node (ref "CLED2") (pin "A") (pinfunction "A_A") (pintype "passive"))
      (node (ref "CLED3") (pin "A") (pinfunction "A_A") (pintype "passive"))
      (node (ref "D1") (pin "ANNODE") (pinfunction "E1_ANNODE") (pintype "passive"))
      (node (ref "J5") (pin "2") (pinfunction "2_2") (pintype "passive"))
      (node (ref "J7") (pin "5") (pinfunction "5_5") (pintype "passive"))
      (node (ref "LED1") (pin "A") (pinfunction "A_A") (pintype "passive"))
      (node (ref "LED2") (pin "A") (pinfunction "A_A") (pintype "passive"))
      (node (ref "PROX") (pin "A") (pinfunction "A_A") (pintype "passive"))
      (node (ref "R10") (pin "1") (pinfunction "1_1") (pintype "passive"))
      (node (ref "R18") (pin "2") (pinfunction "2_2") (pintype "passive"))
      (node (ref "R19") (pin "2") (pinfunction "2_2") (pintype "passive"))
      (node (ref "R2") (pin "3") (pinfunction "3_3") (pintype "passive"))
      (node (ref "R20") (pin "2") (pinfunction "2_2") (pintype "passive"))
      (node (ref "R21") (pin "2") (pinfunction "2_2") (pintype "passive"))
      (node (ref "R22") (pin "1") (pinfunction "1_1") (pintype "passive"))
      (node (ref "R30") (pin "1") (pinfunction "1_1") (pintype "passive"))
      (node (ref "R31") (pin "3") (pinfunction "3_3") (pintype "passive"))
      (node (ref "R32") (pin "2") (pinfunction "2_2") (pintype "passive"))
      (node (ref "R9") (pin "1") (pinfunction "1_1") (pintype "passive"))
      (node (ref "U7") (pin "19") (pinfunction "VDDA2_19") (pintype "bidirectional"))
      (node (ref "U7") (pin "43") (pinfunction "VDDA3_43") (pintype "bidirectional"))
      (node (ref "U7") (pin "47") (pinfunction "VDDD_47") (pintype "bidirectional"))
      (node (ref "U7") (pin "8") (pinfunction "VDDA1_8") (pintype "bidirectional"))
    )
    (net (code "56") (name "VDAC") (class "Default")
      (node (ref "U$1") (pin "A1") (pinfunction "A1_A1") (pintype "bidirectional"))
      (node (ref "U7") (pin "2") (pinfunction "P1[2]_2") (pintype "bidirectional"))
    )
    (net (code "57") (name "VREF") (class "Default")
      (node (ref "C13") (pin "1") (pinfunction "1_1") (pintype "passive"))
      (node (ref "U7") (pin "17") (pinfunction "P2[7]_17") (pintype "bidirectional"))
    )
    (net (code "58") (name "XRES") (class "Default")
      (node (ref "C15") (pin "2") (pinfunction "2_2") (pintype "passive"))
      (node (ref "J7") (pin "3") (pinfunction "3_3") (pintype "passive"))
      (node (ref "R22") (pin "2") (pinfunction "2_2") (pintype "passive"))
      (node (ref "U$1") (pin "RES") (pinfunction "RES_RES") (pintype "bidirectional"))
      (node (ref "U7") (pin "36") (pinfunction "XRES_36") (pintype "bidirectional"))
    )
    (net (code "59") (name "unconnected-(U$1-*D3-PadD3)") (class "Default")
      (node (ref "U$1") (pin "D3") (pinfunction "*D3_D3") (pintype "bidirectional"))
    )
    (net (code "60") (name "unconnected-(U$1-*D6-PadD6)") (class "Default")
      (node (ref "U$1") (pin "D6") (pinfunction "*D6_D6") (pintype "bidirectional"))
    )
    (net (code "61") (name "unconnected-(U$1-*D9-PadD9)") (class "Default")
      (node (ref "U$1") (pin "D9") (pinfunction "*D9_D9") (pintype "bidirectional"))
    )
    (net (code "62") (name "unconnected-(U$1-*D10-PadD10)") (class "Default")
      (node (ref "U$1") (pin "D10") (pinfunction "*D10_D10") (pintype "bidirectional"))
    )
    (net (code "63") (name "unconnected-(U$1-PadA3)") (class "Default")
      (node (ref "U$1") (pin "A3") (pinfunction "A3_A3") (pintype "bidirectional"))
    )
    (net (code "64") (name "unconnected-(U$1-PadA4)") (class "Default")
      (node (ref "U$1") (pin "A4") (pinfunction "A4_A4") (pintype "bidirectional"))
    )
    (net (code "65") (name "unconnected-(U$1-PadA5)") (class "Default")
      (node (ref "U$1") (pin "A5") (pinfunction "A5_A5") (pintype "bidirectional"))
    )
    (net (code "66") (name "unconnected-(U$1-PadAREF)") (class "Default")
      (node (ref "U$1") (pin "AREF") (pinfunction "AREF_AREF") (pintype "bidirectional"))
    )
    (net (code "67") (name "unconnected-(U$1-PadD7)") (class "Default")
      (node (ref "U$1") (pin "D7") (pinfunction "D7_D7") (pintype "bidirectional"))
    )
    (net (code "68") (name "unconnected-(U$1-PadD8)") (class "Default")
      (node (ref "U$1") (pin "D8") (pinfunction "D8_D8") (pintype "bidirectional"))
    )
    (net (code "69") (name "unconnected-(U$1-PadIOREF)") (class "Default")
      (node (ref "U$1") (pin "IOREF") (pinfunction "IOREF_IOREF") (pintype "bidirectional"))
    )
    (net (code "70") (name "unconnected-(U$1-PadVIN)") (class "Default")
      (node (ref "U$1") (pin "VIN") (pinfunction "VIN_VIN") (pintype "bidirectional"))
    )
  )
)
